# 3V3Secondary.net
KiCad netlist of a schematic drawn in Altium Designer
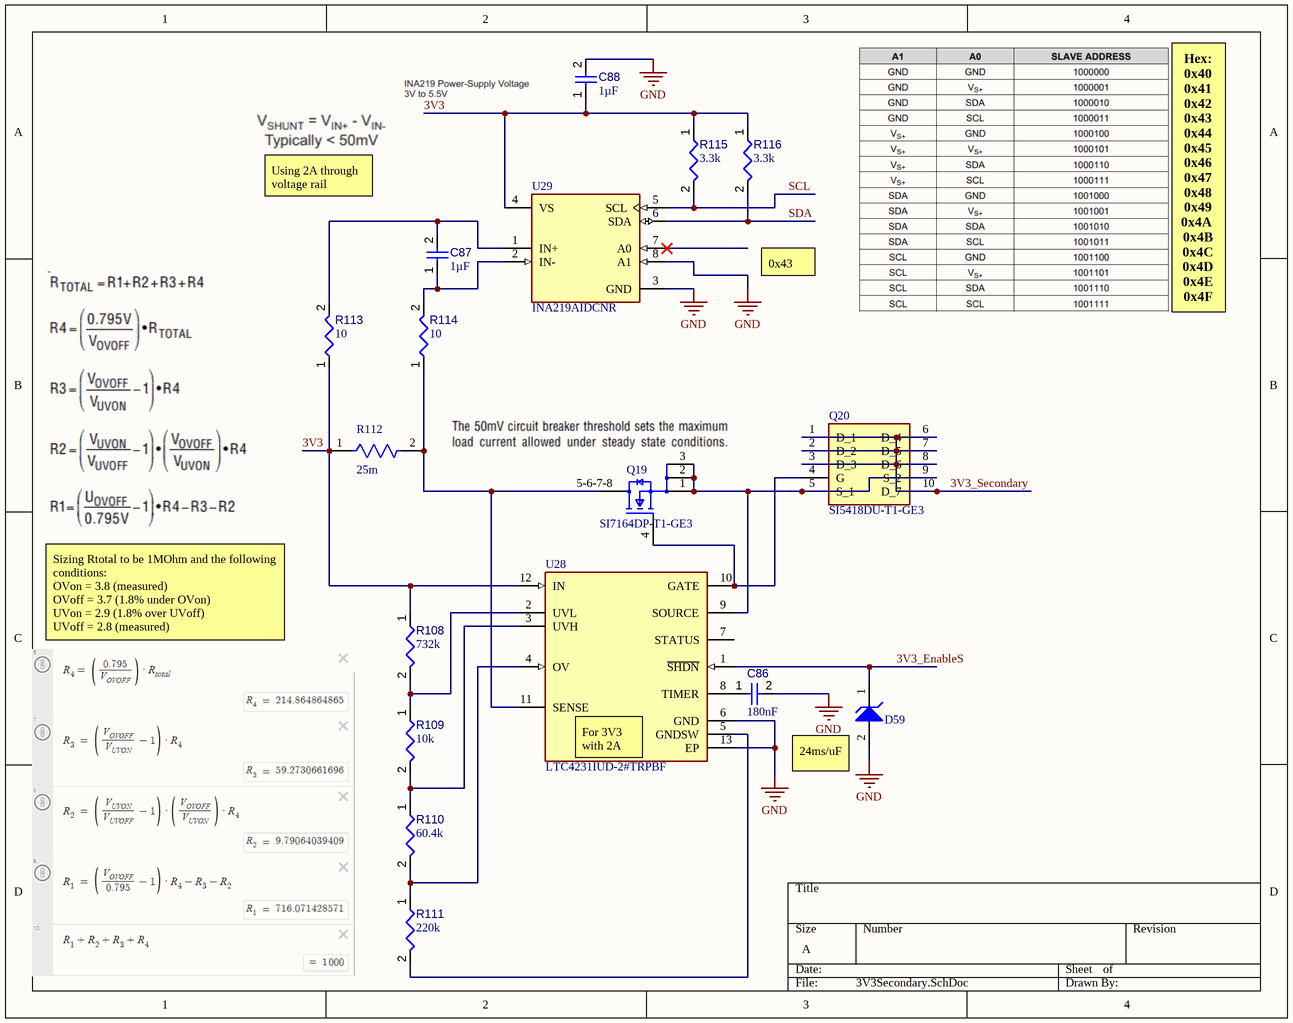
[diagram p0: 3V3Secondary.SchDoc]

(export (version "E")
  (design (tool "Eeschema 10.0.6"))
  (components
    (comp (ref "C86")
      (value "180nF")
      (footprint "FP-C0805C-DN-IPC_A")
      (fields (field (name "Comment") "C0805C184K5RACTU"))
      (libsource (lib "UGA SSRL Hardware Team") (part "CAP-NP-2"))
    )
    (comp (ref "C87")
      (value "1µF")
      (footprint "CAPC1608X90X40LL10T20")
      (description "Chip Capacitor, 1 uF, +/- 10%, 25 V, 0603 (1608 Metric)")
      (fields (field (name "TOLERANCE") "10%") (field (name "Comment") "Capacitor 1 uF +/- 10% 25 V 0603"))
      (libsource (lib "UGA SSRL Hardware Team") (part "CAP-NP-2"))
    )
    (comp (ref "C88")
      (value "1µF")
      (footprint "CAPC1608X90X35ML15T15")
      (description "Chip Capacitor, 1 uF, +/- 10%, 16 V, 0603 (1608 Metric)")
      (fields (field (name "TOLERANCE") "10%") (field (name "Comment") "Capacitor 1uF +/- 10% 16V 0603"))
      (libsource (lib "UGA SSRL Hardware Team") (part "CAP-NP-2"))
    )
    (comp (ref "D59")
      (value "MM3Z3V6T1G")
      (footprint "ONSC-SOD-323-2-477-02_V")
      (description "Zener Voltage Regulator, 300 mW, 2-Pin SOD-323, Pb-Free, Tape and Reel")
      (fields (field (name "MANUFACTURER") "On Semiconductor"))
      (libsource (lib "Altium Content Vault") (part "ONSC-K1A2-2"))
    )
    (comp (ref "Q19")
      (value "SI7164DP-T1-GE3")
      (footprint "Vishay_S17-0173-SINGLE_MFG")
      (libsource (lib "UGA SSRL Hardware Team") (part "SI7164DP-T1-GE3"))
    )
    (comp (ref "Q20")
      (value "SI5418DU-T1-GE3")
      (footprint "SI5418DU-T1-GE3-Footprint-1")
      (libsource (lib "UGA SSRL Hardware Team") (part "SI5418DU-T1-GE3-Symbol-1"))
    )
    (comp (ref "R108")
      (value "732k")
      (footprint "FP-CR0805-IPC_A")
      (fields
        (field (name "POWER") "125mW")
        (field (name "TOLERANCE") "1%")
        (field (name "Comment") "CR0805-FX-7323ELF")
      )
      (libsource (lib "UGA SSRL Hardware Team") (part "RES-2"))
    )
    (comp (ref "R109")
      (value "10k")
      (footprint "RESC1005X40X25ML05T05")
      (description "Chip Resistor, 10 KOhm, +/- 1%, 0.1 W, -55 to 155 degC, 0402 (1005 Metric)")
      (fields (field (name "TOLERANCE") "1%") (field (name "POWER") "100mW"))
      (libsource (lib "UGA SSRL Hardware Team") (part "RES-2"))
    )
    (comp (ref "R110")
      (value "60.4k")
      (footprint "RESC1005X40X25NL05T10")
      (fields
        (field (name "TOLERANCE") "1%")
        (field (name "POWER") "62.5mW")
        (field (name "Comment") "RC0402FR-0760K4L")
      )
      (libsource (lib "UGA SSRL Hardware Team") (part "RES-2"))
    )
    (comp (ref "R111")
      (value "220k")
      (footprint "FP-ESR01-IPC_C")
      (fields
        (field (name "POWER") "200mW")
        (field (name "TOLERANCE") "5%")
        (field (name "Comment") "ESR01MZPJ224")
      )
      (libsource (lib "UGA SSRL Hardware Team") (part "RES-2"))
    )
    (comp (ref "R112")
      (value "CSR1206FK25L0")
      (footprint "FP-CSR1206-IPC_C")
      (description "General Purpose Thick Film Chip Resistor, 1206, 25mΩ, 1%, 0.5W")
      (fields (field (name "RESISTANCE") "25m") (field (name "TOLERANCE") "1%"))
      (libsource (lib "Altium Content Vault") (part "1029c3af85768c4190bb7ad29bc67b5"))
    )
    (comp (ref "R113")
      (value "10")
      (footprint "RESC0402(1005)_L")
      (description "Chip Resistor, 10 Ohms, +/-1 %, 63 mW, -55 to 155 degC, 0402")
      (fields (field (name "TOLERANCE") "1%") (field (name "POWER") "63mW"))
      (libsource (lib "UGA SSRL Hardware Team") (part "RES-2"))
    )
    (comp (ref "R114")
      (value "10")
      (footprint "RESC0402(1005)_L")
      (description "Chip Resistor, 10 Ohms, +/-1 %, 63 mW, -55 to 155 degC, 0402")
      (fields (field (name "TOLERANCE") "1%") (field (name "POWER") "63mW"))
      (libsource (lib "UGA SSRL Hardware Team") (part "RES-2"))
    )
    (comp (ref "R115")
      (value "3.3k")
      (footprint "FP-CRCW1210-e3-IPC_C")
      (fields
        (field (name "TOLERANCE") "5%")
        (field (name "POWER") "500mW")
        (field (name "Comment") "CRCW12103K30JNEA")
      )
      (libsource (lib "UGA SSRL Hardware Team") (part "RES-2"))
    )
    (comp (ref "R116")
      (value "3.3k")
      (footprint "FP-CRCW1210-e3-IPC_C")
      (fields
        (field (name "TOLERANCE") "5%")
        (field (name "POWER") "500mW")
        (field (name "Comment") "CRCW12103K30JNEA")
      )
      (libsource (lib "UGA SSRL Hardware Team") (part "RES-2"))
    )
    (comp (ref "U28")
      (value "LTC4231IUD-2#TRPBF")
      (footprint "FP-UD-12-05-08-1855-IPC_A")
      (description "Switching Controller, CMOS, PQCC12")
      (libsource (lib "UGA SSRL Hardware Team") (part "94c330ae140e2337d879337fe7aaeec"))
    )
    (comp (ref "U29")
      (value "INA219AIDCNR")
      (footprint "FP-DCN0008A-IPC_A")
      (description "Power Supply Support Circuit, Fixed, 2 Channel, 2V, PDSO8")
      (libsource (lib "UGA SSRL Hardware Team") (part "e16934b8ef90d0e345b266f0ae9cd81"))
    )
  )
  (nets
    (net (code "1") (name "/3V3") (class "Default")
      (node (ref "C88") (pin "1") (pinfunction "1_1") (pintype "passive"))
      (node (ref "R108") (pin "1") (pinfunction "1_1") (pintype "passive"))
      (node (ref "R112") (pin "1") (pinfunction "1_1") (pintype "passive"))
      (node (ref "R113") (pin "1") (pinfunction "1_1") (pintype "passive"))
      (node (ref "R115") (pin "1") (pinfunction "1_1") (pintype "passive"))
      (node (ref "R116") (pin "1") (pinfunction "1_1") (pintype "passive"))
      (node (ref "U28") (pin "12") (pinfunction "IN_12") (pintype "input"))
      (node (ref "U29") (pin "4") (pinfunction "VS_4") (pintype "power_in"))
    )
    (net (code "2") (name "/3V3_EnableS") (class "Default")
      (node (ref "D59") (pin "1") (pinfunction "K_1") (pintype "passive"))
      (node (ref "U28") (pin "1") (pinfunction "~{SHDN}_1") (pintype "input"))
    )
    (net (code "3") (name "/3V3_Secondary") (class "Default")
      (node (ref "Q20") (pin "1") (pinfunction "D_1_1") (pintype "passive"))
      (node (ref "Q20") (pin "10") (pinfunction "D_7_10") (pintype "passive"))
      (node (ref "Q20") (pin "2") (pinfunction "D_2_2") (pintype "passive"))
      (node (ref "Q20") (pin "3") (pinfunction "D_3_3") (pintype "passive"))
      (node (ref "Q20") (pin "6") (pinfunction "D_4_6") (pintype "passive"))
      (node (ref "Q20") (pin "7") (pinfunction "D_5_7") (pintype "passive"))
      (node (ref "Q20") (pin "8") (pinfunction "D_6_8") (pintype "passive"))
    )
    (net (code "4") (name "/SCL") (class "Default")
      (node (ref "R115") (pin "2") (pinfunction "2_2") (pintype "passive"))
      (node (ref "U29") (pin "5") (pinfunction "SCL_5") (pintype "input"))
    )
    (net (code "5") (name "/SDA") (class "Default")
      (node (ref "R116") (pin "2") (pinfunction "2_2") (pintype "passive"))
      (node (ref "U29") (pin "6") (pinfunction "SDA_6") (pintype "bidirectional"))
    )
    (net (code "6") (name "GND") (class "Default")
      (node (ref "C86") (pin "2") (pinfunction "2_2") (pintype "passive"))
      (node (ref "C88") (pin "2") (pinfunction "2_2") (pintype "passive"))
      (node (ref "D59") (pin "2") (pinfunction "A_2") (pintype "passive"))
      (node (ref "U28") (pin "13") (pinfunction "EP_13") (pintype "power_in"))
      (node (ref "U28") (pin "6") (pinfunction "GND_6") (pintype "power_in"))
      (node (ref "U29") (pin "3") (pinfunction "GND_3") (pintype "power_in"))
      (node (ref "U29") (pin "8") (pinfunction "A1_8") (pintype "input"))
    )
    (net (code "7") (name "Net-(Q19-D)") (class "Default")
      (node (ref "Q19") (pin "5-6-7-8") (pinfunction "D_5-6-7-8") (pintype "passive"))
      (node (ref "R112") (pin "2") (pinfunction "2_2") (pintype "passive"))
      (node (ref "R114") (pin "1") (pinfunction "1_1") (pintype "passive"))
      (node (ref "U28") (pin "11") (pinfunction "SENSE_11") (pintype "passive"))
    )
    (net (code "8") (name "Net-(Q19-G)") (class "Default")
      (node (ref "Q19") (pin "4") (pinfunction "G_4") (pintype "passive"))
      (node (ref "Q20") (pin "4") (pinfunction "G_4") (pintype "passive"))
      (node (ref "U28") (pin "10") (pinfunction "GATE_10") (pintype "passive"))
    )
    (net (code "9") (name "Net-(Q20-S_1)") (class "Default")
      (node (ref "Q19") (pin "1") (pinfunction "S_1") (pintype "passive"))
      (node (ref "Q19") (pin "2") (pinfunction "S_2") (pintype "passive"))
      (node (ref "Q19") (pin "3") (pinfunction "S_3") (pintype "passive"))
      (node (ref "Q20") (pin "5") (pinfunction "S_1_5") (pintype "passive"))
      (node (ref "Q20") (pin "9") (pinfunction "S_2_9") (pintype "passive"))
      (node (ref "U28") (pin "9") (pinfunction "SOURCE_9") (pintype "passive"))
    )
    (net (code "10") (name "Net-(U28-GNDSW)") (class "Default")
      (node (ref "R111") (pin "2") (pinfunction "2_2") (pintype "passive"))
      (node (ref "U28") (pin "5") (pinfunction "GNDSW_5") (pintype "power_in"))
    )
    (net (code "11") (name "Net-(U28-OV)") (class "Default")
      (node (ref "R110") (pin "2") (pinfunction "2_2") (pintype "passive"))
      (node (ref "R111") (pin "1") (pinfunction "1_1") (pintype "passive"))
      (node (ref "U28") (pin "4") (pinfunction "OV_4") (pintype "input"))
    )
    (net (code "12") (name "Net-(U28-TIMER)") (class "Default")
      (node (ref "C86") (pin "1") (pinfunction "1_1") (pintype "passive"))
      (node (ref "U28") (pin "8") (pinfunction "TIMER_8") (pintype "passive"))
    )
    (net (code "13") (name "Net-(U28-UVH)") (class "Default")
      (node (ref "R109") (pin "2") (pinfunction "2_2") (pintype "passive"))
      (node (ref "R110") (pin "1") (pinfunction "1_1") (pintype "passive"))
      (node (ref "U28") (pin "3") (pinfunction "UVH_3") (pintype "passive"))
    )
    (net (code "14") (name "Net-(U28-UVL)") (class "Default")
      (node (ref "R108") (pin "2") (pinfunction "2_2") (pintype "passive"))
      (node (ref "R109") (pin "1") (pinfunction "1_1") (pintype "passive"))
      (node (ref "U28") (pin "2") (pinfunction "UVL_2") (pintype "passive"))
    )
    (net (code "15") (name "Net-(U29-IN+)") (class "Default")
      (node (ref "C87") (pin "2") (pinfunction "2_2") (pintype "passive"))
      (node (ref "R113") (pin "2") (pinfunction "2_2") (pintype "passive"))
      (node (ref "U29") (pin "1") (pinfunction "IN+_1") (pintype "passive"))
    )
    (net (code "16") (name "Net-(U29-IN-)") (class "Default")
      (node (ref "C87") (pin "1") (pinfunction "1_1") (pintype "passive"))
      (node (ref "R114") (pin "2") (pinfunction "2_2") (pintype "passive"))
      (node (ref "U29") (pin "2") (pinfunction "IN-_2") (pintype "input"))
    )
    (net (code "17") (name "unconnected-(U28-STATUS-Pad7)") (class "Default")
      (node (ref "U28") (pin "7") (pinfunction "STATUS_7") (pintype "passive"))
    )
    (net (code "18") (name "unconnected-(U29-A0-Pad7)") (class "Default")
      (node (ref "U29") (pin "7") (pinfunction "A0_7") (pintype "input+no_connect"))
    )
  )
)
